# h2oiq.net
KiCad netlist of a schematic drawn in EAGLE
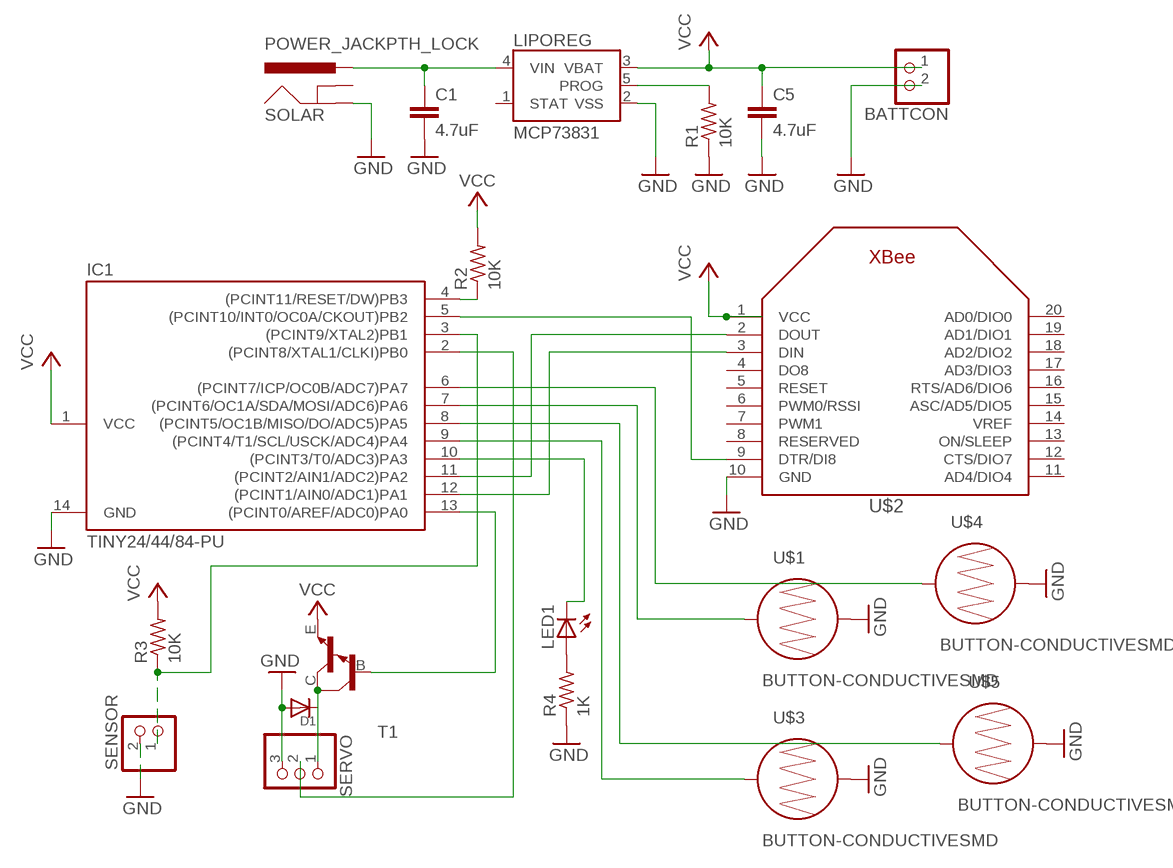
[diagram p0: schematic, sheet 1]

(export (version "E")
  (design (tool "Eeschema 10.0.6"))
  (components
    (comp (ref "BATTCON")
      (value "JST_2PIN-SMT")
      (footprint "eagle-import:JST-PH-2-SMT")
      (libsource (lib "eagle-import") (part "JST_2PIN-SMT"))
    )
    (comp (ref "C1")
      (value "4.7uF")
      (footprint "eagle-import:0402-CAP")
      (libsource (lib "eagle-import") (part "CAP0402-CAP"))
    )
    (comp (ref "C5")
      (value "4.7uF")
      (footprint "eagle-import:0402-CAP")
      (libsource (lib "eagle-import") (part "CAP0402-CAP"))
    )
    (comp (ref "D1")
      (value "DIODESMA")
      (footprint "eagle-import:SMADIODE")
      (libsource (lib "eagle-import") (part "DIODESMA"))
    )
    (comp (ref "IC1")
      (value "TINY24/44/84-PU")
      (footprint "eagle-import:DIL14")
      (libsource (lib "eagle-import") (part "TINY24/44/84-PU"))
    )
    (comp (ref "LED1")
      (value "LED5MM")
      (footprint "eagle-import:LED5MM")
      (libsource (lib "eagle-import") (part "LED5MM"))
    )
    (comp (ref "LIPOREG")
      (value "MCP73831")
      (footprint "eagle-import:SOT23-5")
      (libsource (lib "eagle-import") (part "MCP73831"))
    )
    (comp (ref "R1")
      (value "10K")
      (footprint "eagle-import:M1206")
      (libsource (lib "eagle-import") (part "R-US_M1206"))
    )
    (comp (ref "R2")
      (value "10K")
      (footprint "eagle-import:M1206")
      (libsource (lib "eagle-import") (part "R-US_M1206"))
    )
    (comp (ref "R3")
      (value "10K")
      (footprint "eagle-import:M1206")
      (libsource (lib "eagle-import") (part "R-US_M1206"))
    )
    (comp (ref "R4")
      (value "1K")
      (footprint "eagle-import:M1206")
      (libsource (lib "eagle-import") (part "R-US_M1206"))
    )
    (comp (ref "SENSOR")
      (value "JST_2PIN-SMT")
      (footprint "eagle-import:JST-PH-2-SMT")
      (libsource (lib "eagle-import") (part "JST_2PIN-SMT"))
    )
    (comp (ref "SERVO")
      (value "PINHD-1X3CB")
      (footprint "eagle-import:1X03-CLEANBIG")
      (libsource (lib "eagle-import") (part "PINHD-1X3CB"))
    )
    (comp (ref "SOLAR")
      (value "POWER_JACKPTH_LOCK")
      (footprint "eagle-import:POWER_JACK_PTH_LOCK")
      (libsource (lib "eagle-import") (part "POWER_JACKPTH_LOCK"))
    )
    (comp (ref "T1")
      (value "MMBTA13LT1-NPN_DARL-SOT23-BEC")
      (footprint "eagle-import:SOT23-BEC")
      (libsource (lib "eagle-import") (part "-NPN_DARL-SOT23-BECMMBTA13LT1"))
    )
    (comp (ref "U$1")
      (value "BUTTON-CONDUCTIVESMD")
      (footprint "eagle-import:BUTTON-CONDUCTIVE")
      (libsource (lib "eagle-import") (part "BUTTON-CONDUCTIVESMD"))
    )
    (comp (ref "U$2")
      (value "XBEE")
      (footprint "eagle-import:XBEE")
      (libsource (lib "eagle-import") (part "XBEE"))
    )
    (comp (ref "U$3")
      (value "BUTTON-CONDUCTIVESMD")
      (footprint "eagle-import:BUTTON-CONDUCTIVE")
      (libsource (lib "eagle-import") (part "BUTTON-CONDUCTIVESMD"))
    )
    (comp (ref "U$4")
      (value "BUTTON-CONDUCTIVESMD")
      (footprint "eagle-import:BUTTON-CONDUCTIVE")
      (libsource (lib "eagle-import") (part "BUTTON-CONDUCTIVESMD"))
    )
    (comp (ref "U$5")
      (value "BUTTON-CONDUCTIVESMD")
      (footprint "eagle-import:BUTTON-CONDUCTIVE")
      (libsource (lib "eagle-import") (part "BUTTON-CONDUCTIVESMD"))
    )
  )
  (nets
    (net (code "1") (name "GND") (class "Default")
      (node (ref "BATTCON") (pin "2") (pinfunction "1_2") (pintype "passive"))
      (node (ref "C1") (pin "2") (pinfunction "2_2") (pintype "passive"))
      (node (ref "C5") (pin "2") (pinfunction "2_2") (pintype "passive"))
      (node (ref "D1") (pin "A") (pinfunction "A_A") (pintype "passive"))
      (node (ref "IC1") (pin "14") (pinfunction "GND_14") (pintype "power_in"))
      (node (ref "LIPOREG") (pin "2") (pinfunction "VSS_2") (pintype "power_in"))
      (node (ref "R1") (pin "1") (pinfunction "1_1") (pintype "passive"))
      (node (ref "R4") (pin "1") (pinfunction "1_1") (pintype "passive"))
      (node (ref "SENSOR") (pin "2") (pinfunction "1_2") (pintype "passive"))
      (node (ref "SERVO") (pin "3") (pinfunction "3_3") (pintype "passive"))
      (node (ref "SOLAR") (pin "GND") (pinfunction "GND_GND") (pintype "bidirectional"))
      (node (ref "U$1") (pin "2") (pinfunction "2_2") (pintype "passive"))
      (node (ref "U$2") (pin "10") (pinfunction "GND_10") (pintype "power_in"))
      (node (ref "U$3") (pin "2") (pinfunction "2_2") (pintype "passive"))
      (node (ref "U$4") (pin "2") (pinfunction "2_2") (pintype "passive"))
      (node (ref "U$5") (pin "2") (pinfunction "2_2") (pintype "passive"))
    )
    (net (code "2") (name "Net-(D1-PadC)") (class "Default")
      (node (ref "D1") (pin "C") (pinfunction "C_C") (pintype "passive"))
      (node (ref "SERVO") (pin "1") (pinfunction "1_1") (pintype "passive"))
      (node (ref "T1") (pin "C") (pinfunction "C_C") (pintype "passive"))
    )
    (net (code "3") (name "Net-(IC1-(PCINT0{slash}AREF{slash}ADC0)PA0)") (class "Default")
      (node (ref "IC1") (pin "13") (pinfunction "(PCINT0/AREF/ADC0)PA0_13") (pintype "bidirectional"))
      (node (ref "T1") (pin "B") (pinfunction "B_B") (pintype "passive"))
    )
    (net (code "4") (name "Net-(IC1-(PCINT1{slash}AIN0{slash}ADC1)PA1)") (class "Default")
      (node (ref "IC1") (pin "12") (pinfunction "(PCINT1/AIN0/ADC1)PA1_12") (pintype "bidirectional"))
      (node (ref "U$2") (pin "3") (pinfunction "DIN_3") (pintype "input"))
    )
    (net (code "5") (name "Net-(IC1-(PCINT2{slash}AIN1{slash}ADC2)PA2)") (class "Default")
      (node (ref "IC1") (pin "11") (pinfunction "(PCINT2/AIN1/ADC2)PA2_11") (pintype "bidirectional"))
      (node (ref "U$2") (pin "2") (pinfunction "DOUT_2") (pintype "output"))
    )
    (net (code "6") (name "Net-(IC1-(PCINT3{slash}T0{slash}ADC3)PA3)") (class "Default")
      (node (ref "IC1") (pin "10") (pinfunction "(PCINT3/T0/ADC3)PA3_10") (pintype "bidirectional"))
      (node (ref "LED1") (pin "K") (pinfunction "C_K") (pintype "passive"))
    )
    (net (code "7") (name "Net-(IC1-(PCINT4{slash}T1{slash}SCL{slash}USCK{slash}ADC4)PA4)") (class "Default")
      (node (ref "IC1") (pin "9") (pinfunction "(PCINT4/T1/SCL/USCK/ADC4)PA4_9") (pintype "bidirectional"))
      (node (ref "U$3") (pin "1") (pinfunction "1_1") (pintype "passive"))
    )
    (net (code "8") (name "Net-(IC1-(PCINT5{slash}OC1B{slash}MISO{slash}DO{slash}ADC5)PA5)") (class "Default")
      (node (ref "IC1") (pin "8") (pinfunction "(PCINT5/OC1B/MISO/DO/ADC5)PA5_8") (pintype "bidirectional"))
      (node (ref "U$5") (pin "1") (pinfunction "1_1") (pintype "passive"))
    )
    (net (code "9") (name "Net-(IC1-(PCINT6{slash}OC1A{slash}SDA{slash}MOSI{slash}ADC6)PA6)") (class "Default")
      (node (ref "IC1") (pin "7") (pinfunction "(PCINT6/OC1A/SDA/MOSI/ADC6)PA6_7") (pintype "bidirectional"))
      (node (ref "U$1") (pin "1") (pinfunction "1_1") (pintype "passive"))
    )
    (net (code "10") (name "Net-(IC1-(PCINT7{slash}ICP{slash}OC0B{slash}ADC7)PA7)") (class "Default")
      (node (ref "IC1") (pin "6") (pinfunction "(PCINT7/ICP/OC0B/ADC7)PA7_6") (pintype "bidirectional"))
      (node (ref "U$4") (pin "1") (pinfunction "1_1") (pintype "passive"))
    )
    (net (code "11") (name "Net-(IC1-(PCINT8{slash}XTAL1{slash}CLKI)PB0)") (class "Default")
      (node (ref "IC1") (pin "2") (pinfunction "(PCINT8/XTAL1/CLKI)PB0_2") (pintype "bidirectional"))
      (node (ref "SERVO") (pin "2") (pinfunction "2_2") (pintype "passive"))
    )
    (net (code "12") (name "Net-(IC1-(PCINT9{slash}XTAL2)PB1)") (class "Default")
      (node (ref "IC1") (pin "3") (pinfunction "(PCINT9/XTAL2)PB1_3") (pintype "bidirectional"))
      (node (ref "R3") (pin "1") (pinfunction "1_1") (pintype "passive"))
      (node (ref "SENSOR") (pin "1") (pinfunction "2_1") (pintype "passive"))
    )
    (net (code "13") (name "Net-(IC1-(PCINT10{slash}INT0{slash}OC0A{slash}CKOUT)PB2)") (class "Default")
      (node (ref "IC1") (pin "5") (pinfunction "(PCINT10/INT0/OC0A/CKOUT)PB2_5") (pintype "bidirectional"))
      (node (ref "U$2") (pin "9") (pinfunction "DTR/DI8_9") (pintype "input"))
    )
    (net (code "14") (name "Net-(IC1-(PCINT11{slash}RESET{slash}DW)PB3)") (class "Default")
      (node (ref "IC1") (pin "4") (pinfunction "(PCINT11/RESET/DW)PB3_4") (pintype "bidirectional"))
      (node (ref "R2") (pin "1") (pinfunction "1_1") (pintype "passive"))
    )
    (net (code "15") (name "Net-(LED1-PadA)") (class "Default")
      (node (ref "LED1") (pin "A") (pinfunction "A_A") (pintype "passive"))
      (node (ref "R4") (pin "2") (pinfunction "2_2") (pintype "passive"))
    )
    (net (code "16") (name "Net-(LIPOREG-PROG)") (class "Default")
      (node (ref "LIPOREG") (pin "5") (pinfunction "PROG_5") (pintype "input"))
      (node (ref "R1") (pin "2") (pinfunction "2_2") (pintype "passive"))
    )
    (net (code "17") (name "Net-(LIPOREG-VIN)") (class "Default")
      (node (ref "C1") (pin "1") (pinfunction "1_1") (pintype "passive"))
      (node (ref "LIPOREG") (pin "4") (pinfunction "VIN_4") (pintype "power_in"))
      (node (ref "SOLAR") (pin "PWR") (pinfunction "PWR_PWR") (pintype "bidirectional"))
    )
    (net (code "18") (name "VCC") (class "Default")
      (node (ref "BATTCON") (pin "1") (pinfunction "2_1") (pintype "passive"))
      (node (ref "C5") (pin "1") (pinfunction "1_1") (pintype "passive"))
      (node (ref "IC1") (pin "1") (pinfunction "VCC_1") (pintype "power_in"))
      (node (ref "LIPOREG") (pin "3") (pinfunction "VBAT_3") (pintype "power_in"))
      (node (ref "R2") (pin "2") (pinfunction "2_2") (pintype "passive"))
      (node (ref "R3") (pin "2") (pinfunction "2_2") (pintype "passive"))
      (node (ref "T1") (pin "E") (pinfunction "E_E") (pintype "passive"))
      (node (ref "U$2") (pin "1") (pinfunction "VCC_1") (pintype "power_in"))
    )
    (net (code "19") (name "unconnected-(LIPOREG-STAT-Pad1)") (class "Default")
      (node (ref "LIPOREG") (pin "1") (pinfunction "STAT_1") (pintype "output"))
    )
    (net (code "20") (name "unconnected-(SOLAR-PadGNDBREAK)") (class "Default")
      (node (ref "SOLAR") (pin "GNDBREAK") (pinfunction "GNDBREAK_GNDBREAK") (pintype "bidirectional"))
    )
    (net (code "21") (name "unconnected-(U$2-AD0{slash}DIO0-Pad20)") (class "Default")
      (node (ref "U$2") (pin "20") (pinfunction "AD0/DIO0_20") (pintype "bidirectional"))
    )
    (net (code "22") (name "unconnected-(U$2-AD1{slash}DIO1-Pad19)") (class "Default")
      (node (ref "U$2") (pin "19") (pinfunction "AD1/DIO1_19") (pintype "bidirectional"))
    )
    (net (code "23") (name "unconnected-(U$2-AD2{slash}DIO2-Pad18)") (class "Default")
      (node (ref "U$2") (pin "18") (pinfunction "AD2/DIO2_18") (pintype "bidirectional"))
    )
    (net (code "24") (name "unconnected-(U$2-AD3{slash}DIO3-Pad17)") (class "Default")
      (node (ref "U$2") (pin "17") (pinfunction "AD3/DIO3_17") (pintype "bidirectional"))
    )
    (net (code "25") (name "unconnected-(U$2-AD4{slash}DIO4-Pad11)") (class "Default")
      (node (ref "U$2") (pin "11") (pinfunction "AD4/DIO4_11") (pintype "bidirectional"))
    )
    (net (code "26") (name "unconnected-(U$2-ASC{slash}AD5{slash}DIO5-Pad15)") (class "Default")
      (node (ref "U$2") (pin "15") (pinfunction "ASC/AD5/DIO5_15") (pintype "bidirectional"))
    )
    (net (code "27") (name "unconnected-(U$2-CTS{slash}DIO7-Pad12)") (class "Default")
      (node (ref "U$2") (pin "12") (pinfunction "CTS/DIO7_12") (pintype "bidirectional"))
    )
    (net (code "28") (name "unconnected-(U$2-DO8-Pad4)") (class "Default")
      (node (ref "U$2") (pin "4") (pinfunction "DO8_4") (pintype "output"))
    )
    (net (code "29") (name "unconnected-(U$2-ON{slash}SLEEP-Pad13)") (class "Default")
      (node (ref "U$2") (pin "13") (pinfunction "ON/SLEEP_13") (pintype "output"))
    )
    (net (code "30") (name "unconnected-(U$2-PWM0{slash}RSSI-Pad6)") (class "Default")
      (node (ref "U$2") (pin "6") (pinfunction "PWM0/RSSI_6") (pintype "output"))
    )
    (net (code "31") (name "unconnected-(U$2-PWM1-Pad7)") (class "Default")
      (node (ref "U$2") (pin "7") (pinfunction "PWM1_7") (pintype "output"))
    )
    (net (code "32") (name "unconnected-(U$2-RESERVED-Pad8)") (class "Default")
      (node (ref "U$2") (pin "8") (pinfunction "RESERVED_8") (pintype "no_connect"))
    )
    (net (code "33") (name "unconnected-(U$2-RESET-Pad5)") (class "Default")
      (node (ref "U$2") (pin "5") (pinfunction "RESET_5") (pintype "input"))
    )
    (net (code "34") (name "unconnected-(U$2-RTS{slash}AD6{slash}DIO6-Pad16)") (class "Default")
      (node (ref "U$2") (pin "16") (pinfunction "RTS/AD6/DIO6_16") (pintype "bidirectional"))
    )
    (net (code "35") (name "unconnected-(U$2-VREF-Pad14)") (class "Default")
      (node (ref "U$2") (pin "14") (pinfunction "VREF_14") (pintype "input"))
    )
  )
)
